# ConvertidorBuck.net
KiCad netlist of a schematic drawn in Altium Designer
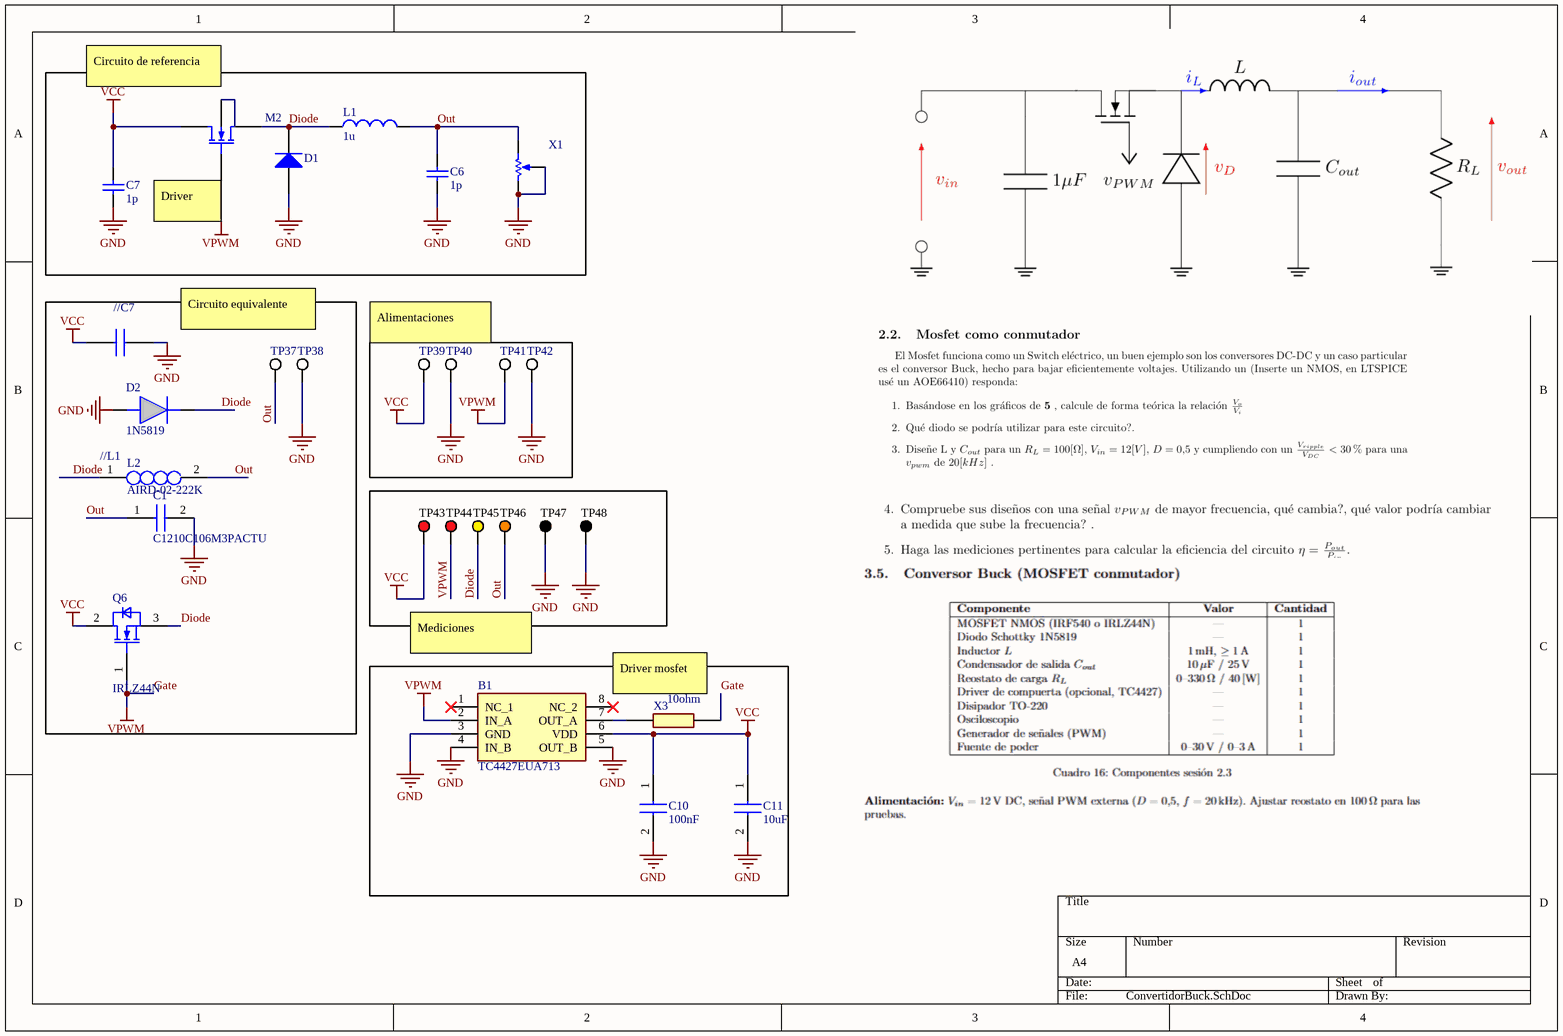
[diagram p0: ConvertidorBuck.SchDoc]

(export (version "E")
  (design (tool "Eeschema 10.0.6"))
  (components
    (comp (ref "B1")
      (value "TC4427EUA713")
      (footprint "SOP65P490X110-8N")
      (description "TC4427A Series 1.5 A 18 Vmax 7 Ohm Dual Non Inverting MOSFET Driver - MSOP-8")
      (fields (field (name "MOUSER PART NUMBER") "579-TC4427EUA713"))
      (libsource (lib "TC4427EUA713") (part "TC4427EUA713"))
    )
    (comp (ref "C1")
      (value "C1210C106M3PACTU")
      (footprint "Cap10uF:C1210")
      (description "Capacitor")
      (fields (field (name "MOUSER PART NUMBER") "80-C1210C106M3P"))
      (libsource (lib "Cap10uF") (part "C1210C106M3PACTU"))
    )
    (comp (ref "C6")
      (value "1p")
      (description "Capacitor")
      (libsource (lib "Simulation Generic Components") (part "Capacitor"))
    )
    (comp (ref "C7")
      (value "1p")
      (description "Capacitor")
      (libsource (lib "Simulation Generic Components") (part "Capacitor"))
    )
    (comp (ref "C8")
      (value "C1206C105K3RAC7800")
      (footprint "CAPC3216X140N")
      (description "Multilayer Ceramic Capacitors MLCC - SMD/SMT 25V 1uF X7R 1206 10%")
      (fields (field (name "MOUSER PART NUMBER") "80-C1206C105K3R7800"))
      (libsource (lib "Cap1uF") (part "C1206C105K3RAC7800"))
    )
    (comp (ref "C10")
      (value "100nF")
      (footprint "Cap100nF:C0603")
      (description "Capacitor")
      (fields
        (field (name "MANUFACTURER_PART_NUMBER") "C0603X104M3RACTU")
        (field (name "MOUSER PART NUMBER") "80-C0603X104M3R")
      )
      (libsource (lib "Cap100nF") (part "C0603X104M3RACTU"))
    )
    (comp (ref "C11")
      (value "10uF")
      (footprint "Cap10uF:C1210")
      (description "Capacitor")
      (fields
        (field (name "MANUFACTURER_PART_NUMBER") "C1210C106M3PACTU")
        (field (name "MOUSER PART NUMBER") "80-C1210C106M3P")
      )
      (libsource (lib "Cap10uF") (part "C1210C106M3PACTU"))
    )
    (comp (ref "D1") (value "Diode") (libsource (lib "Simulation Generic Components") (part "Diode")))
    (comp (ref "D2")
      (value "1N5819")
      (footprint "DIOAD1408W86L464D236")
      (description "Schottky Barrier Rectifier Diodes")
      (fields (field (name "MOUSER PART NUMBER") "637-1N5819"))
      (libsource (lib "1N5819") (part "1N5819"))
    )
    (comp (ref "L1")
      (value "1u")
      (description "Inductor")
      (libsource (lib "Simulation Generic Components") (part "Inductor"))
    )
    (comp (ref "L2")
      (value "AIRD-02-222K")
      (footprint "Inductor2.2mH:AIRD-02")
      (description "Inductor")
      (fields (field (name "MOUSER PART NUMBER") "815-AIRD-02-222K"))
      (libsource (lib "Inductor2.2mH") (part "AIRD-02-222K"))
    )
    (comp (ref "M2")
      (value "N-channel MOS1 MOSFET Shichman and Hodges Model")
      (libsource (lib "Simulation Generic Components") (part "MOSFET N-ch Lev1"))
    )
    (comp (ref "Q6")
      (value "IRLZ44N")
      (footprint "IFX-PG-TO220-3-904-1")
      (description "OptiMOS 3 Power-Transistor, VDS 100V")
      (fields (field (name "MANUFACTURER") "Infineon Technologies"))
      (libsource (lib "IRLZ44N") (part "IRLZ44N"))
    )
    (comp (ref "TP37")
      (value "575-4")
      (footprint "KSTN-575-4")
      (description "Banana Jack, Non-Insulated, 1-Pin THD, RoHS, Bulk")
      (fields (field (name "MANUFACTURER") "Keystone-Electronics"))
      (libsource (lib "Altium Content Vault") (part "TESTPOINT_WHITE"))
    )
    (comp (ref "TP38")
      (value "575-4")
      (footprint "KSTN-575-4")
      (description "Banana Jack, Non-Insulated, 1-Pin THD, RoHS, Bulk")
      (fields (field (name "MANUFACTURER") "Keystone-Electronics"))
      (libsource (lib "Altium Content Vault") (part "TESTPOINT_WHITE"))
    )
    (comp (ref "TP39")
      (value "575-4")
      (footprint "KSTN-575-4")
      (description "Banana Jack, Non-Insulated, 1-Pin THD, RoHS, Bulk")
      (fields (field (name "MANUFACTURER") "Keystone-Electronics"))
      (libsource (lib "Altium Content Vault") (part "TESTPOINT_WHITE"))
    )
    (comp (ref "TP40")
      (value "575-4")
      (footprint "KSTN-575-4")
      (description "Banana Jack, Non-Insulated, 1-Pin THD, RoHS, Bulk")
      (fields (field (name "MANUFACTURER") "Keystone-Electronics"))
      (libsource (lib "Altium Content Vault") (part "TESTPOINT_WHITE"))
    )
    (comp (ref "TP41")
      (value "575-4")
      (footprint "KSTN-575-4")
      (description "Banana Jack, Non-Insulated, 1-Pin THD, RoHS, Bulk")
      (fields (field (name "MANUFACTURER") "Keystone-Electronics"))
      (libsource (lib "Altium Content Vault") (part "TESTPOINT_WHITE"))
    )
    (comp (ref "TP42")
      (value "575-4")
      (footprint "KSTN-575-4")
      (description "Banana Jack, Non-Insulated, 1-Pin THD, RoHS, Bulk")
      (fields (field (name "MANUFACTURER") "Keystone-Electronics"))
      (libsource (lib "Altium Content Vault") (part "TESTPOINT_WHITE"))
    )
    (comp (ref "TP43")
      (value "5010")
      (footprint "KSTN-5010_V")
      (description "Test Point, Red, Through Hole, RoHS, Bulk")
      (fields (field (name "MANUFACTURER") "Keystone"))
      (libsource (lib "Altium Content Vault") (part "TESTPOINT_RED"))
    )
    (comp (ref "TP44")
      (value "5010")
      (footprint "KSTN-5010_V")
      (description "Test Point, Red, Through Hole, RoHS, Bulk")
      (fields (field (name "MANUFACTURER") "Keystone"))
      (libsource (lib "Altium Content Vault") (part "TESTPOINT_RED"))
    )
    (comp (ref "TP45")
      (value "5014")
      (footprint "KSTN-5014_V")
      (description "Test Point, Yellow, Through Hole, RoHS, Bulk")
      (fields (field (name "MANUFACTURER") "Keystone"))
      (libsource (lib "Altium Content Vault") (part "TESTPOINT_YELLOW"))
    )
    (comp (ref "TP46")
      (value "5013")
      (footprint "KSTN-5013_V")
      (description "Test Point, Orange, Through Hole, RoHS, Bulk")
      (fields (field (name "MANUFACTURER") "Keystone"))
      (libsource (lib "Altium Content Vault") (part "TESTPOINT_ORANGE"))
    )
    (comp (ref "TP47")
      (value "5011")
      (footprint "KSTN-5011_V")
      (description "Test Point, Black, Through Hole, RoHS, Bulk")
      (fields (field (name "MANUFACTURER") "Keystone"))
      (libsource (lib "Altium Content Vault") (part "TESTPOINT_BLACK"))
    )
    (comp (ref "TP48")
      (value "5011")
      (footprint "KSTN-5011_V")
      (description "Test Point, Black, Through Hole, RoHS, Bulk")
      (fields (field (name "MANUFACTURER") "Keystone"))
      (libsource (lib "Altium Content Vault") (part "TESTPOINT_BLACK"))
    )
    (comp (ref "X1")
      (value "Potentiometer")
      (libsource (lib "Simulation Generic Components") (part "Potentiometer"))
    )
    (comp (ref "X3")
      (value "10ohm")
      (footprint "RESC3216X60N")
      (description "Standard Thick Film Chip Resistors value 10R0 ohm.")
      (fields (field (name "MANUFACTURER_PART_NUMBER") "CRCW120610R0FKTC"))
      (libsource (lib "Resistencia10Ohm") (part "CRCW120610R0FKTC"))
    )
  )
  (nets
    (net (code "1") (name "/Diode") (class "Default")
      (node (ref "D1") (pin "2") (pinfunction "K_2") (pintype "passive"))
      (node (ref "D2") (pin "1") (pinfunction "K_1") (pintype "passive"))
      (node (ref "L1") (pin "1") (pinfunction "1_1") (pintype "passive"))
      (node (ref "L2") (pin "1") (pinfunction "1_1") (pintype "passive"))
      (node (ref "M2") (pin "3") (pinfunction "S_3") (pintype "passive"))
      (node (ref "Q6") (pin "3") (pinfunction "SOURCE_3") (pintype "passive"))
      (node (ref "TP45") (pin "1") (pinfunction "1_1") (pintype "passive"))
    )
    (net (code "2") (name "/Out") (class "Default")
      (node (ref "C1") (pin "1") (pinfunction "1_1") (pintype "passive"))
      (node (ref "C6") (pin "1") (pinfunction "1_1") (pintype "passive"))
      (node (ref "L1") (pin "2") (pinfunction "2_2") (pintype "passive"))
      (node (ref "L2") (pin "2") (pinfunction "2_2") (pintype "passive"))
      (node (ref "TP37") (pin "1") (pinfunction "1_1") (pintype "passive"))
      (node (ref "TP46") (pin "1") (pinfunction "1_1") (pintype "passive"))
      (node (ref "X1") (pin "1") (pinfunction "TOP_1") (pintype "passive"))
    )
    (net (code "3") (name "GND") (class "Default")
      (node (ref "B1") (pin "3") (pinfunction "GND_3") (pintype "passive"))
      (node (ref "B1") (pin "4") (pinfunction "IN_B_4") (pintype "passive"))
      (node (ref "B1") (pin "5") (pinfunction "OUT_B_5") (pintype "passive"))
      (node (ref "C1") (pin "2") (pinfunction "2_2") (pintype "passive"))
      (node (ref "C10") (pin "2") (pinfunction "2_2") (pintype "passive"))
      (node (ref "C11") (pin "2") (pinfunction "2_2") (pintype "passive"))
      (node (ref "C6") (pin "2") (pinfunction "2_2") (pintype "passive"))
      (node (ref "C7") (pin "2") (pinfunction "2_2") (pintype "passive"))
      (node (ref "C8") (pin "2") (pinfunction "2_2") (pintype "passive"))
      (node (ref "D1") (pin "1") (pinfunction "A_1") (pintype "passive"))
      (node (ref "D2") (pin "2") (pinfunction "A_2") (pintype "passive"))
      (node (ref "TP38") (pin "1") (pinfunction "1_1") (pintype "passive"))
      (node (ref "TP40") (pin "1") (pinfunction "1_1") (pintype "passive"))
      (node (ref "TP42") (pin "1") (pinfunction "1_1") (pintype "passive"))
      (node (ref "TP47") (pin "1") (pinfunction "1_1") (pintype "passive"))
      (node (ref "TP48") (pin "1") (pinfunction "1_1") (pintype "passive"))
      (node (ref "X1") (pin "2") (pinfunction "BOT_2") (pintype "passive"))
      (node (ref "X1") (pin "3") (pinfunction "TAP_3") (pintype "passive"))
    )
    (net (code "4") (name "Net-(B1-OUT_A)") (class "Default")
      (node (ref "B1") (pin "7") (pinfunction "OUT_A_7") (pintype "passive"))
      (node (ref "X3") (pin "1") (pinfunction "1_1") (pintype "passive"))
    )
    (net (code "5") (name "VCC") (class "Default")
      (node (ref "B1") (pin "6") (pinfunction "VDD_6") (pintype "passive"))
      (node (ref "C10") (pin "1") (pinfunction "1_1") (pintype "passive"))
      (node (ref "C11") (pin "1") (pinfunction "1_1") (pintype "passive"))
      (node (ref "C7") (pin "1") (pinfunction "1_1") (pintype "passive"))
      (node (ref "C8") (pin "1") (pinfunction "1_1") (pintype "passive"))
      (node (ref "M2") (pin "1") (pinfunction "D_1") (pintype "passive"))
      (node (ref "Q6") (pin "2") (pinfunction "DRAIN_2") (pintype "passive"))
      (node (ref "TP39") (pin "1") (pinfunction "1_1") (pintype "passive"))
      (node (ref "TP43") (pin "1") (pinfunction "1_1") (pintype "passive"))
    )
    (net (code "6") (name "VPWM") (class "Default")
      (node (ref "B1") (pin "2") (pinfunction "IN_A_2") (pintype "passive"))
      (node (ref "M2") (pin "2") (pinfunction "G_2") (pintype "passive"))
      (node (ref "Q6") (pin "1") (pinfunction "GATE_1") (pintype "passive"))
      (node (ref "TP41") (pin "1") (pinfunction "1_1") (pintype "passive"))
      (node (ref "TP44") (pin "1") (pinfunction "1_1") (pintype "passive"))
      (node (ref "X3") (pin "2") (pinfunction "2_2") (pintype "passive"))
    )
    (net (code "7") (name "unconnected-(B1-NC_1-Pad1)") (class "Default")
      (node (ref "B1") (pin "1") (pinfunction "NC_1_1") (pintype "passive+no_connect"))
    )
    (net (code "8") (name "unconnected-(B1-NC_2-Pad8)") (class "Default")
      (node (ref "B1") (pin "8") (pinfunction "NC_2_8") (pintype "passive+no_connect"))
    )
    (net (code "9") (name "unconnected-(M2-B-Pad4)") (class "Default")
      (node (ref "M2") (pin "4") (pinfunction "B_4") (pintype "passive"))
    )
  )
)
